# Sheet1_Analog.net
KiCad netlist of a schematic drawn in Altium Designer
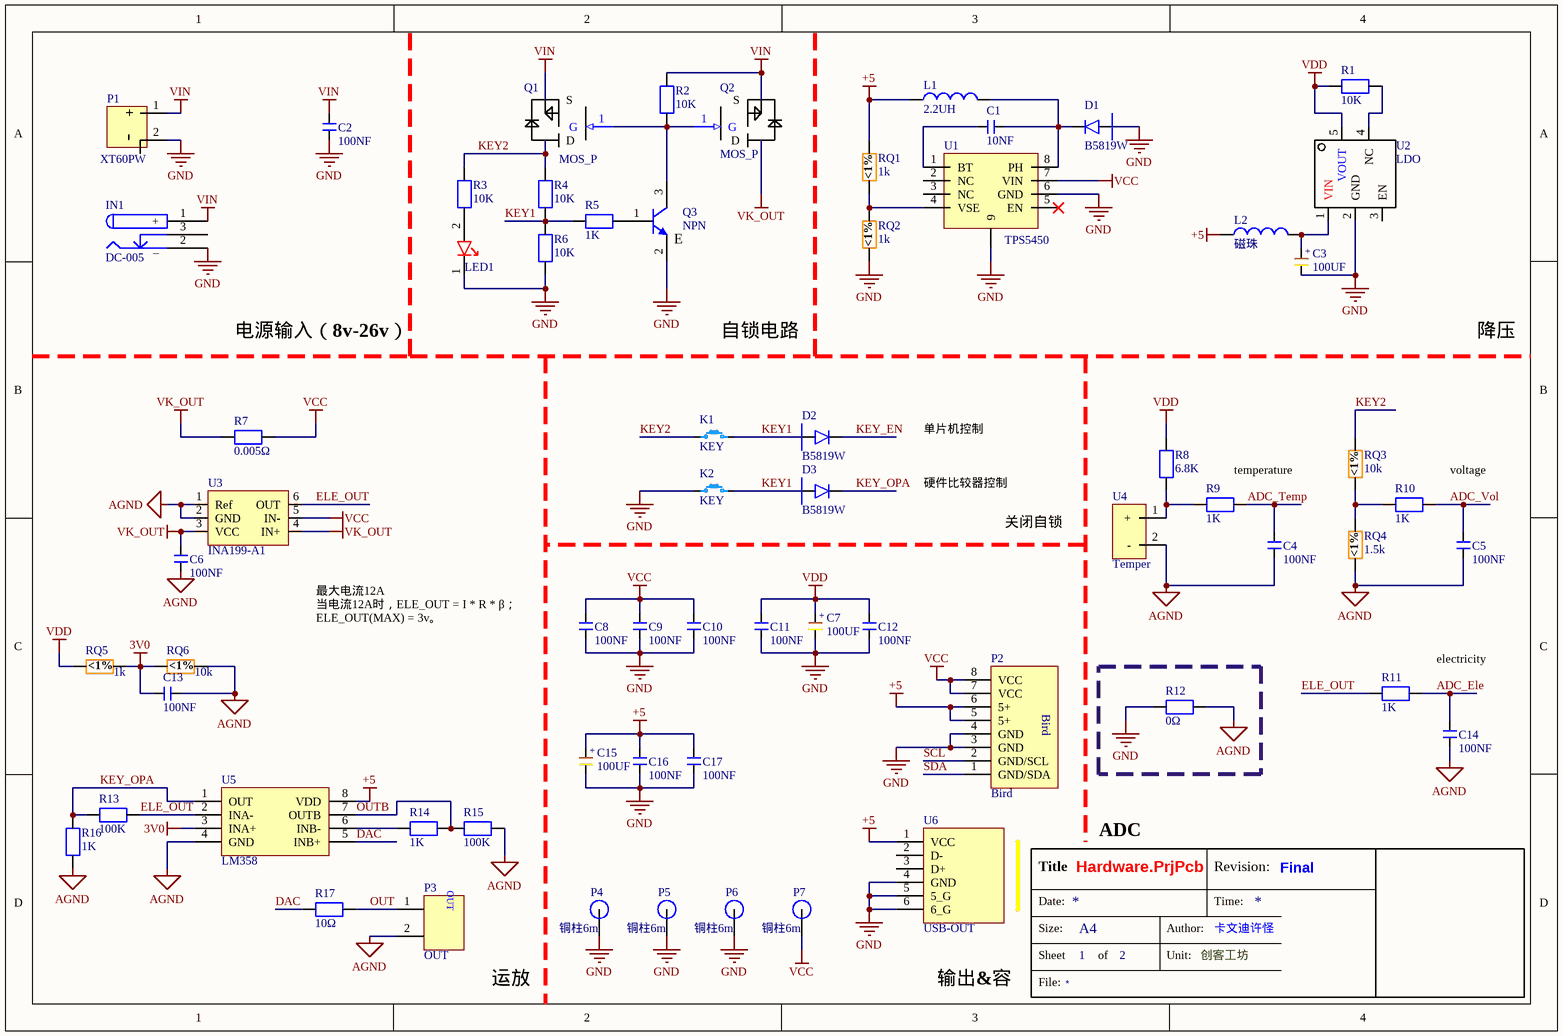
[diagram p0: Sheet1_Analog.SchDoc]

(export (version "E")
  (design (tool "Eeschema 10.0.6"))
  (components
    (comp (ref "C1")
      (value "10NF")
      (footprint "CAP_0603")
      (description "CAP  12~50V")
      (libsource (lib "User") (part "CAP"))
    )
    (comp (ref "C2")
      (value "100NF")
      (footprint "CAP_0603")
      (description "CAP  12~50V")
      (libsource (lib "User") (part "CAP"))
    )
    (comp (ref "C3")
      (value "100UF")
      (footprint "CAP_6032_C")
      (description "CAP  6~12V  钽电容")
      (libsource (lib "User") (part "CAP_TA"))
    )
    (comp (ref "C4")
      (value "100NF")
      (footprint "CAP_0603")
      (description "CAP  12~50V")
      (libsource (lib "User") (part "CAP"))
    )
    (comp (ref "C5")
      (value "100NF")
      (footprint "CAP_0603")
      (description "CAP  12~50V")
      (libsource (lib "User") (part "CAP"))
    )
    (comp (ref "C6")
      (value "100NF")
      (footprint "CAP_0603")
      (description "CAP  12~50V")
      (libsource (lib "User") (part "CAP"))
    )
    (comp (ref "C7")
      (value "100UF")
      (footprint "CAP_6032_C")
      (description "CAP  6~12V  钽电容")
      (libsource (lib "User") (part "CAP_TA"))
    )
    (comp (ref "C8")
      (value "100NF")
      (footprint "CAP_0603")
      (description "CAP  12~50V")
      (libsource (lib "User") (part "CAP"))
    )
    (comp (ref "C9")
      (value "100NF")
      (footprint "CAP_1206")
      (description "CAP  12~50V")
      (libsource (lib "User") (part "CAP"))
    )
    (comp (ref "C10")
      (value "100NF")
      (footprint "CAP_0603")
      (description "CAP  12~50V")
      (libsource (lib "User") (part "CAP"))
    )
    (comp (ref "C11")
      (value "100NF")
      (footprint "CAP_0603")
      (description "CAP  12~50V")
      (libsource (lib "User") (part "CAP"))
    )
    (comp (ref "C12")
      (value "100NF")
      (footprint "CAP_0603")
      (description "CAP  12~50V")
      (libsource (lib "User") (part "CAP"))
    )
    (comp (ref "C13")
      (value "100NF")
      (footprint "CAP_0603")
      (description "CAP  12~50V")
      (libsource (lib "User") (part "CAP"))
    )
    (comp (ref "C14")
      (value "100NF")
      (footprint "CAP_0603")
      (description "CAP  12~50V")
      (libsource (lib "User") (part "CAP"))
    )
    (comp (ref "C15")
      (value "100UF")
      (footprint "CAP_6032_C")
      (description "CAP  6~12V  钽电容")
      (libsource (lib "User") (part "CAP_TA"))
    )
    (comp (ref "C16")
      (value "100NF")
      (footprint "CAP_0603")
      (description "CAP  12~50V")
      (libsource (lib "User") (part "CAP"))
    )
    (comp (ref "C17")
      (value "100NF")
      (footprint "CAP_0603")
      (description "CAP  12~50V")
      (libsource (lib "User") (part "CAP"))
    )
    (comp (ref "D1")
      (value "B5819W")
      (footprint "DIODE-SMB")
      (description "Diode_肖特基/二极管")
      (libsource (lib "User") (part "Diode-SM"))
    )
    (comp (ref "D2")
      (value "B5819W")
      (footprint "DIODE_SOD123")
      (description "Diode_肖特基/二极管")
      (libsource (lib "User") (part "Diode-SM"))
    )
    (comp (ref "D3")
      (value "B5819W")
      (footprint "DIODE_SOD123")
      (description "Diode_肖特基/二极管")
      (libsource (lib "User") (part "Diode-SM"))
    )
    (comp (ref "IN1")
      (value "DC-005")
      (footprint "AC-DC-SMT")
      (description "Interface")
      (libsource (lib "User") (part "DC002"))
    )
    (comp (ref "K1")
      (value "KEY")
      (footprint "KEY-C-Side-3")
      (description "Key")
      (libsource (lib "User") (part "KEY"))
    )
    (comp (ref "K2")
      (value "KEY")
      (footprint "KEY-C-Side-3")
      (description "Key")
      (libsource (lib "User") (part "KEY"))
    )
    (comp (ref "L1")
      (value "2.2UH")
      (footprint "INDUCTANCE_0630")
      (description "Inductor")
      (fields (field (name "PUBLISHER") "Altium Limited"))
      (libsource (lib "User") (part "Inductor"))
    )
    (comp (ref "L2")
      (value "磁珠")
      (footprint "Inductor_0603")
      (description "Inductor")
      (fields (field (name "PUBLISHER") "Altium Limited"))
      (libsource (lib "User") (part "Inductor"))
    )
    (comp (ref "LED1")
      (value "LED_R/G/B/Y")
      (footprint "LED_0603_R")
      (description "LED")
      (libsource (lib "User") (part "LED_SMT"))
    )
    (comp (ref "P1")
      (value "XT60PW")
      (footprint "XT60-PW-M20")
      (description "Interface")
      (libsource (lib "User") (part "XT60"))
    )
    (comp (ref "P2")
      (value "Bird")
      (footprint "XH2.54-WS-8P")
      (description "Header")
      (libsource (lib "User") (part "Bird_8pin"))
    )
    (comp (ref "P3")
      (value "OUT")
      (footprint "XH2.54-WS-2P")
      (description "Header")
      (libsource (lib "User") (part "OUT_2PIN"))
    )
    (comp (ref "P4")
      (value "铜柱6m")
      (footprint "M3x6_L-Type")
      (description "IN-OUT")
      (libsource (lib "User") (part "Pillar"))
    )
    (comp (ref "P5")
      (value "铜柱6m")
      (footprint "M3x6_L-Type")
      (description "IN-OUT")
      (libsource (lib "User") (part "Pillar"))
    )
    (comp (ref "P6")
      (value "铜柱6m")
      (footprint "M3x6_L-Type")
      (description "IN-OUT")
      (libsource (lib "User") (part "Pillar"))
    )
    (comp (ref "P7")
      (value "铜柱6m")
      (footprint "M3x6_L-Type")
      (description "IN-OUT")
      (libsource (lib "User") (part "Pillar"))
    )
    (comp (ref "Q1")
      (value "MOS_P")
      (footprint "SOT23_3")
      (description "MOS")
      (libsource (lib "User") (part "MOSFET_P"))
    )
    (comp (ref "Q2")
      (value "MOS_P")
      (footprint "TO252_2")
      (description "MOS")
      (libsource (lib "User") (part "MOSFET_P"))
    )
    (comp (ref "Q3") (value "NPN") (footprint "SOT23_3") (libsource (lib "User") (part "NPN")))
    (comp (ref "R1")
      (value "10K")
      (footprint "RESC_0603_2")
      (description "RES 贴片")
      (libsource (lib "User") (part "RES"))
    )
    (comp (ref "R2")
      (value "10K")
      (footprint "RESC_0603_2")
      (description "RES 贴片")
      (libsource (lib "User") (part "RES"))
    )
    (comp (ref "R3")
      (value "10K")
      (footprint "RESC_0603_2")
      (description "RES 贴片")
      (libsource (lib "User") (part "RES"))
    )
    (comp (ref "R4")
      (value "10K")
      (footprint "RESC_0603_2")
      (description "RES 贴片")
      (libsource (lib "User") (part "RES"))
    )
    (comp (ref "R5")
      (value "1K")
      (footprint "RESC_0603_2")
      (description "RES 贴片")
      (libsource (lib "User") (part "RES"))
    )
    (comp (ref "R6")
      (value "10K")
      (footprint "RESC_0603_2")
      (description "RES 贴片")
      (libsource (lib "User") (part "RES"))
    )
    (comp (ref "R7")
      (value "0.005Ω")
      (footprint "2512")
      (description "RES 贴片")
      (libsource (lib "User") (part "RES"))
    )
    (comp (ref "R8")
      (value "6.8K")
      (footprint "RESC_0603_2")
      (description "RES 贴片")
      (libsource (lib "User") (part "RES"))
    )
    (comp (ref "R9")
      (value "1K")
      (footprint "RESC_0603_2")
      (description "RES 贴片")
      (libsource (lib "User") (part "RES"))
    )
    (comp (ref "R10")
      (value "1K")
      (footprint "RESC_0603_2")
      (description "RES 贴片")
      (libsource (lib "User") (part "RES"))
    )
    (comp (ref "R11")
      (value "1K")
      (footprint "RESC_0603_2")
      (description "RES 贴片")
      (libsource (lib "User") (part "RES"))
    )
    (comp (ref "R12")
      (value "0Ω")
      (footprint "RESC_0603_2")
      (description "RES 贴片")
      (libsource (lib "User") (part "RES"))
    )
    (comp (ref "R13")
      (value "100K")
      (footprint "RESC_0603_2")
      (description "RES 贴片")
      (libsource (lib "User") (part "RES"))
    )
    (comp (ref "R14")
      (value "1K")
      (footprint "RESC_0603_2")
      (description "RES 贴片")
      (libsource (lib "User") (part "RES"))
    )
    (comp (ref "R15")
      (value "100K")
      (footprint "RESC_0603_2")
      (description "RES 贴片")
      (libsource (lib "User") (part "RES"))
    )
    (comp (ref "R16")
      (value "1K")
      (footprint "RESC_0603_2")
      (description "RES 贴片")
      (libsource (lib "User") (part "RES"))
    )
    (comp (ref "R17")
      (value "10Ω")
      (footprint "RESC_0603_2")
      (description "RES 贴片")
      (libsource (lib "User") (part "RES"))
    )
    (comp (ref "RQ1")
      (value "1k")
      (footprint "RESC_0603_2")
      (description "RES")
      (libsource (lib "User") (part "RES_quality"))
    )
    (comp (ref "RQ2")
      (value "1k")
      (footprint "RESC_0603_2")
      (description "RES")
      (libsource (lib "User") (part "RES_quality"))
    )
    (comp (ref "RQ3")
      (value "10k")
      (footprint "RESC_0603_2")
      (description "RES")
      (libsource (lib "User") (part "RES_quality"))
    )
    (comp (ref "RQ4")
      (value "1.5k")
      (footprint "RESC_0603_2")
      (description "RES")
      (libsource (lib "User") (part "RES_quality"))
    )
    (comp (ref "RQ5")
      (value "1k")
      (footprint "RESC_0603_2")
      (description "RES")
      (libsource (lib "User") (part "RES_quality"))
    )
    (comp (ref "RQ6")
      (value "10k")
      (footprint "RESC_0603_2")
      (description "RES")
      (libsource (lib "User") (part "RES_quality"))
    )
    (comp (ref "U1")
      (value "TPS5450")
      (footprint "SOIC_8E")
      (description "DC-DC")
      (libsource (lib "User") (part "TPS5450DDAR"))
    )
    (comp (ref "U2")
      (value "LDO")
      (footprint "SOT23_5")
      (description "LDO  3.3V  500ma")
      (libsource (lib "User") (part "LDO_SOT23-5"))
    )
    (comp (ref "U3")
      (value "INA199-A1")
      (footprint "SOT-363")
      (description "INA199-A1_6PIN")
      (libsource (lib "User") (part "INA199"))
    )
    (comp (ref "U4")
      (value "Temper")
      (footprint "RESC_0603_1")
      (description "Mode")
      (libsource (lib "User") (part "Temper"))
    )
    (comp (ref "U5")
      (value "LM358")
      (footprint "MSOP_8")
      (description "OPA,5v")
      (libsource (lib "User") (part "LM(v)358"))
    )
    (comp (ref "U6")
      (value "USB-OUT")
      (footprint "USB-A/F-S")
      (description "USB")
      (libsource (lib "User") (part "USB-OUT"))
    )
  )
  (nets
    (net (code "1") (name "+5") (class "Default")
      (node (ref "C15") (pin "1") (pinfunction "0_1") (pintype "passive"))
      (node (ref "C16") (pin "2") (pinfunction "0_2") (pintype "passive"))
      (node (ref "C17") (pin "2") (pinfunction "0_2") (pintype "passive"))
      (node (ref "L1") (pin "1") (pinfunction "1_1") (pintype "passive"))
      (node (ref "L2") (pin "1") (pinfunction "1_1") (pintype "passive"))
      (node (ref "P2") (pin "5") (pinfunction "5+_5") (pintype "passive"))
      (node (ref "P2") (pin "6") (pinfunction "5+_6") (pintype "passive"))
      (node (ref "RQ1") (pin "2") (pinfunction "2_2") (pintype "passive"))
      (node (ref "U5") (pin "8") (pinfunction "VDD_8") (pintype "passive"))
      (node (ref "U6") (pin "1") (pinfunction "VCC_1") (pintype "passive"))
    )
    (net (code "2") (name "/ADC_Ele") (class "Default")
      (node (ref "C14") (pin "2") (pinfunction "0_2") (pintype "passive"))
      (node (ref "R11") (pin "2") (pinfunction "2_2") (pintype "passive"))
    )
    (net (code "3") (name "/ADC_Temp") (class "Default")
      (node (ref "C4") (pin "2") (pinfunction "0_2") (pintype "passive"))
      (node (ref "R9") (pin "2") (pinfunction "2_2") (pintype "passive"))
    )
    (net (code "4") (name "/ADC_Vol") (class "Default")
      (node (ref "C5") (pin "2") (pinfunction "0_2") (pintype "passive"))
      (node (ref "R10") (pin "2") (pinfunction "2_2") (pintype "passive"))
    )
    (net (code "5") (name "/DAC") (class "Default")
      (node (ref "R17") (pin "2") (pinfunction "2_2") (pintype "passive"))
      (node (ref "U5") (pin "5") (pinfunction "INB+_5") (pintype "passive"))
    )
    (net (code "6") (name "/ELE_OUT") (class "Default")
      (node (ref "R11") (pin "1") (pinfunction "1_1") (pintype "passive"))
      (node (ref "R13") (pin "1") (pinfunction "1_1") (pintype "passive"))
      (node (ref "U3") (pin "6") (pinfunction "OUT_6") (pintype "passive"))
      (node (ref "U5") (pin "2") (pinfunction "INA-_2") (pintype "passive"))
    )
    (net (code "7") (name "/KEY1") (class "Default")
      (node (ref "D2") (pin "1") (pinfunction "P_1") (pintype "passive"))
      (node (ref "D3") (pin "1") (pinfunction "P_1") (pintype "passive"))
      (node (ref "K1") (pin "1") (pintype "passive"))
      (node (ref "K2") (pin "1") (pintype "passive"))
      (node (ref "R4") (pin "1") (pinfunction "1_1") (pintype "passive"))
      (node (ref "R5") (pin "1") (pinfunction "1_1") (pintype "passive"))
      (node (ref "R6") (pin "2") (pinfunction "2_2") (pintype "passive"))
    )
    (net (code "8") (name "/KEY2") (class "Default")
      (node (ref "K1") (pin "2") (pintype "passive"))
      (node (ref "Q1") (pin "3") (pinfunction "D_3") (pintype "passive"))
      (node (ref "R3") (pin "2") (pinfunction "2_2") (pintype "passive"))
      (node (ref "R4") (pin "2") (pinfunction "2_2") (pintype "passive"))
      (node (ref "RQ3") (pin "2") (pinfunction "2_2") (pintype "passive"))
    )
    (net (code "9") (name "/KEY_EN") (class "Default")
      (node (ref "D2") (pin "2") (pinfunction "N_2") (pintype "passive"))
    )
    (net (code "10") (name "/KEY_OPA") (class "Default")
      (node (ref "D3") (pin "2") (pinfunction "N_2") (pintype "passive"))
      (node (ref "R13") (pin "2") (pinfunction "2_2") (pintype "passive"))
      (node (ref "R16") (pin "2") (pinfunction "2_2") (pintype "passive"))
      (node (ref "U5") (pin "1") (pinfunction "OUT_1") (pintype "passive"))
    )
    (net (code "11") (name "/OUT") (class "Default")
      (node (ref "P3") (pin "1") (pintype "passive"))
      (node (ref "R17") (pin "1") (pinfunction "1_1") (pintype "passive"))
    )
    (net (code "12") (name "/OUTB") (class "Default")
      (node (ref "R14") (pin "1") (pinfunction "1_1") (pintype "passive"))
      (node (ref "R15") (pin "2") (pinfunction "2_2") (pintype "passive"))
      (node (ref "U5") (pin "7") (pinfunction "OUTB_7") (pintype "passive"))
    )
    (net (code "13") (name "/SCL") (class "Default")
      (node (ref "P2") (pin "2") (pinfunction "GND/SCL_2") (pintype "passive"))
    )
    (net (code "14") (name "/SDA") (class "Default")
      (node (ref "P2") (pin "1") (pinfunction "GND/SDA_1") (pintype "passive"))
    )
    (net (code "15") (name "3V0") (class "Default")
      (node (ref "C13") (pin "2") (pinfunction "0_2") (pintype "passive"))
      (node (ref "RQ5") (pin "2") (pinfunction "2_2") (pintype "passive"))
      (node (ref "RQ6") (pin "1") (pinfunction "1_1") (pintype "passive"))
      (node (ref "U5") (pin "3") (pinfunction "INA+_3") (pintype "passive"))
    )
    (net (code "16") (name "AGND") (class "Default")
      (node (ref "C13") (pin "1") (pinfunction "0_1") (pintype "passive"))
      (node (ref "C14") (pin "1") (pinfunction "0_1") (pintype "passive"))
      (node (ref "C4") (pin "1") (pinfunction "0_1") (pintype "passive"))
      (node (ref "C5") (pin "1") (pinfunction "0_1") (pintype "passive"))
      (node (ref "C6") (pin "1") (pinfunction "0_1") (pintype "passive"))
      (node (ref "P3") (pin "2") (pintype "passive"))
      (node (ref "R12") (pin "2") (pinfunction "2_2") (pintype "passive"))
      (node (ref "R15") (pin "1") (pinfunction "1_1") (pintype "passive"))
      (node (ref "R16") (pin "1") (pinfunction "1_1") (pintype "passive"))
      (node (ref "RQ4") (pin "1") (pinfunction "1_1") (pintype "passive"))
      (node (ref "RQ6") (pin "2") (pinfunction "2_2") (pintype "passive"))
      (node (ref "U3") (pin "1") (pinfunction "Ref_1") (pintype "passive"))
      (node (ref "U3") (pin "2") (pinfunction "GND_2") (pintype "passive"))
      (node (ref "U4") (pin "2") (pinfunction "-_2") (pintype "passive"))
      (node (ref "U5") (pin "4") (pinfunction "GND_4") (pintype "passive"))
    )
    (net (code "17") (name "GND") (class "Default")
      (node (ref "C10") (pin "1") (pinfunction "0_1") (pintype "passive"))
      (node (ref "C11") (pin "1") (pinfunction "0_1") (pintype "passive"))
      (node (ref "C12") (pin "1") (pinfunction "0_1") (pintype "passive"))
      (node (ref "C15") (pin "2") (pinfunction "0_2") (pintype "passive"))
      (node (ref "C16") (pin "1") (pinfunction "0_1") (pintype "passive"))
      (node (ref "C17") (pin "1") (pinfunction "0_1") (pintype "passive"))
      (node (ref "C2") (pin "1") (pinfunction "0_1") (pintype "passive"))
      (node (ref "C3") (pin "2") (pinfunction "0_2") (pintype "passive"))
      (node (ref "C7") (pin "2") (pinfunction "0_2") (pintype "passive"))
      (node (ref "C8") (pin "1") (pinfunction "0_1") (pintype "passive"))
      (node (ref "C9") (pin "1") (pinfunction "0_1") (pintype "passive"))
      (node (ref "D1") (pin "1") (pinfunction "P_1") (pintype "passive"))
      (node (ref "IN1") (pin "2") (pinfunction "__2") (pintype "passive"))
      (node (ref "K2") (pin "2") (pintype "passive"))
      (node (ref "LED1") (pin "1") (pinfunction "-_1") (pintype "passive"))
      (node (ref "P1") (pin "2") (pinfunction "-_2") (pintype "passive"))
      (node (ref "P2") (pin "3") (pinfunction "GND_3") (pintype "passive"))
      (node (ref "P2") (pin "4") (pinfunction "GND_4") (pintype "passive"))
      (node (ref "P4") (pin "1") (pinfunction "IO_1") (pintype "passive"))
      (node (ref "P5") (pin "1") (pinfunction "IO_1") (pintype "passive"))
      (node (ref "P6") (pin "1") (pinfunction "IO_1") (pintype "passive"))
      (node (ref "Q3") (pin "2") (pinfunction "E_2") (pintype "passive"))
      (node (ref "R12") (pin "1") (pinfunction "1_1") (pintype "passive"))
      (node (ref "R6") (pin "1") (pinfunction "1_1") (pintype "passive"))
      (node (ref "RQ2") (pin "1") (pinfunction "1_1") (pintype "passive"))
      (node (ref "U1") (pin "6") (pinfunction "GND_6") (pintype "passive"))
      (node (ref "U1") (pin "9") (pinfunction "9_9") (pintype "passive"))
      (node (ref "U2") (pin "2") (pinfunction "GND_2") (pintype "passive"))
      (node (ref "U6") (pin "4") (pinfunction "GND_4") (pintype "passive"))
      (node (ref "U6") (pin "5") (pinfunction "5_G_5") (pintype "passive"))
      (node (ref "U6") (pin "6") (pinfunction "6_G_6") (pintype "passive"))
    )
    (net (code "18") (name "Net-(D1-N)") (class "Default")
      (node (ref "C1") (pin "1") (pinfunction "0_1") (pintype "passive"))
      (node (ref "D1") (pin "2") (pinfunction "N_2") (pintype "passive"))
      (node (ref "L1") (pin "2") (pinfunction "2_2") (pintype "passive"))
      (node (ref "U1") (pin "8") (pinfunction "PH_8") (pintype "passive"))
    )
    (net (code "19") (name "Net-(LED1-+)") (class "Default")
      (node (ref "LED1") (pin "2") (pinfunction "+_2") (pintype "passive"))
      (node (ref "R3") (pin "1") (pinfunction "1_1") (pintype "passive"))
    )
    (net (code "20") (name "Net-(Q1-G)") (class "Default")
      (node (ref "Q1") (pin "1") (pinfunction "G_1") (pintype "input"))
      (node (ref "Q2") (pin "1") (pinfunction "G_1") (pintype "input"))
      (node (ref "Q3") (pin "3") (pinfunction "C_3") (pintype "passive"))
      (node (ref "R2") (pin "1") (pinfunction "1_1") (pintype "passive"))
    )
    (net (code "21") (name "Net-(Q3-B)") (class "Default")
      (node (ref "Q3") (pin "1") (pinfunction "B_1") (pintype "passive"))
      (node (ref "R5") (pin "2") (pinfunction "2_2") (pintype "passive"))
    )
    (net (code "22") (name "Net-(R10-Pad1)") (class "Default")
      (node (ref "R10") (pin "1") (pinfunction "1_1") (pintype "passive"))
      (node (ref "RQ3") (pin "1") (pinfunction "1_1") (pintype "passive"))
      (node (ref "RQ4") (pin "2") (pinfunction "2_2") (pintype "passive"))
    )
    (net (code "23") (name "Net-(U1-BT)") (class "Default")
      (node (ref "C1") (pin "2") (pinfunction "0_2") (pintype "passive"))
      (node (ref "U1") (pin "1") (pinfunction "BT_1") (pintype "passive"))
    )
    (net (code "24") (name "Net-(U1-VSE)") (class "Default")
      (node (ref "RQ1") (pin "1") (pinfunction "1_1") (pintype "passive"))
      (node (ref "RQ2") (pin "2") (pinfunction "2_2") (pintype "passive"))
      (node (ref "U1") (pin "4") (pinfunction "VSE_4") (pintype "passive"))
    )
    (net (code "25") (name "Net-(U2-NC)") (class "Default")
      (node (ref "R1") (pin "1") (pinfunction "1_1") (pintype "passive"))
      (node (ref "U2") (pin "4") (pinfunction "NC_4") (pintype "passive"))
    )
    (net (code "26") (name "Net-(U2-VIN)") (class "Default")
      (node (ref "C3") (pin "1") (pinfunction "0_1") (pintype "passive"))
      (node (ref "L2") (pin "2") (pinfunction "2_2") (pintype "passive"))
      (node (ref "U2") (pin "1") (pinfunction "VIN_1") (pintype "passive"))
    )
    (net (code "27") (name "Net-(U4-+)") (class "Default")
      (node (ref "R8") (pin "2") (pinfunction "2_2") (pintype "passive"))
      (node (ref "R9") (pin "1") (pinfunction "1_1") (pintype "passive"))
      (node (ref "U4") (pin "1") (pinfunction "+_1") (pintype "passive"))
    )
    (net (code "28") (name "Net-(U5-INB-)") (class "Default")
      (node (ref "R14") (pin "2") (pinfunction "2_2") (pintype "passive"))
      (node (ref "U5") (pin "6") (pinfunction "INB-_6") (pintype "passive"))
    )
    (net (code "29") (name "VCC") (class "Default")
      (node (ref "C10") (pin "2") (pinfunction "0_2") (pintype "passive"))
      (node (ref "C8") (pin "2") (pinfunction "0_2") (pintype "passive"))
      (node (ref "C9") (pin "2") (pinfunction "0_2") (pintype "passive"))
      (node (ref "P2") (pin "7") (pinfunction "VCC_7") (pintype "passive"))
      (node (ref "P2") (pin "8") (pinfunction "VCC_8") (pintype "passive"))
      (node (ref "P7") (pin "1") (pinfunction "IO_1") (pintype "passive"))
      (node (ref "R7") (pin "2") (pinfunction "2_2") (pintype "passive"))
      (node (ref "U1") (pin "7") (pinfunction "VIN_7") (pintype "passive"))
      (node (ref "U3") (pin "5") (pinfunction "IN-_5") (pintype "passive"))
    )
    (net (code "30") (name "VDD") (class "Default")
      (node (ref "C11") (pin "2") (pinfunction "0_2") (pintype "passive"))
      (node (ref "C12") (pin "2") (pinfunction "0_2") (pintype "passive"))
      (node (ref "C7") (pin "1") (pinfunction "0_1") (pintype "passive"))
      (node (ref "R1") (pin "2") (pinfunction "2_2") (pintype "passive"))
      (node (ref "R8") (pin "1") (pinfunction "1_1") (pintype "passive"))
      (node (ref "RQ5") (pin "1") (pinfunction "1_1") (pintype "passive"))
      (node (ref "U2") (pin "5") (pinfunction "VOUT_5") (pintype "passive"))
    )
    (net (code "31") (name "VIN") (class "Default")
      (node (ref "C2") (pin "2") (pinfunction "0_2") (pintype "passive"))
      (node (ref "IN1") (pin "1") (pinfunction "+_1") (pintype "passive"))
      (node (ref "P1") (pin "1") (pinfunction "+_1") (pintype "passive"))
      (node (ref "Q1") (pin "2") (pinfunction "S_2") (pintype "passive"))
      (node (ref "Q2") (pin "2") (pinfunction "S_2") (pintype "passive"))
      (node (ref "R2") (pin "2") (pinfunction "2_2") (pintype "passive"))
    )
    (net (code "32") (name "VK_OUT") (class "Default")
      (node (ref "C6") (pin "2") (pinfunction "0_2") (pintype "passive"))
      (node (ref "Q2") (pin "3") (pinfunction "D_3") (pintype "passive"))
      (node (ref "R7") (pin "1") (pinfunction "1_1") (pintype "passive"))
      (node (ref "U3") (pin "3") (pinfunction "VCC_3") (pintype "passive"))
      (node (ref "U3") (pin "4") (pinfunction "IN+_4") (pintype "passive"))
    )
    (net (code "33") (name "unconnected-(IN1-_-Pad3)") (class "Default")
      (node (ref "IN1") (pin "3") (pinfunction "__3") (pintype "passive"))
    )
    (net (code "34") (name "unconnected-(P1---Pad0)") (class "Default")
      (node (ref "P1") (pin "0") (pinfunction "-_0") (pintype "passive"))
    )
    (net (code "35") (name "unconnected-(U1-EN-Pad5)") (class "Default")
      (node (ref "U1") (pin "5") (pinfunction "EN_5") (pintype "passive+no_connect"))
    )
    (net (code "36") (name "unconnected-(U1-NC-Pad2)") (class "Default")
      (node (ref "U1") (pin "2") (pinfunction "NC_2") (pintype "passive"))
    )
    (net (code "37") (name "unconnected-(U1-NC-Pad3)") (class "Default")
      (node (ref "U1") (pin "3") (pinfunction "NC_3") (pintype "passive"))
    )
    (net (code "38") (name "unconnected-(U2-EN-Pad3)") (class "Default")
      (node (ref "U2") (pin "3") (pinfunction "EN_3") (pintype "passive"))
    )
    (net (code "39") (name "unconnected-(U6-D+-Pad3)") (class "Default")
      (node (ref "U6") (pin "3") (pinfunction "D+_3") (pintype "passive"))
    )
    (net (code "40") (name "unconnected-(U6-D--Pad2)") (class "Default")
      (node (ref "U6") (pin "2") (pinfunction "D-_2") (pintype "passive"))
    )
  )
)
